# MainSchematic.net
KiCad netlist of a schematic drawn in Altium Designer
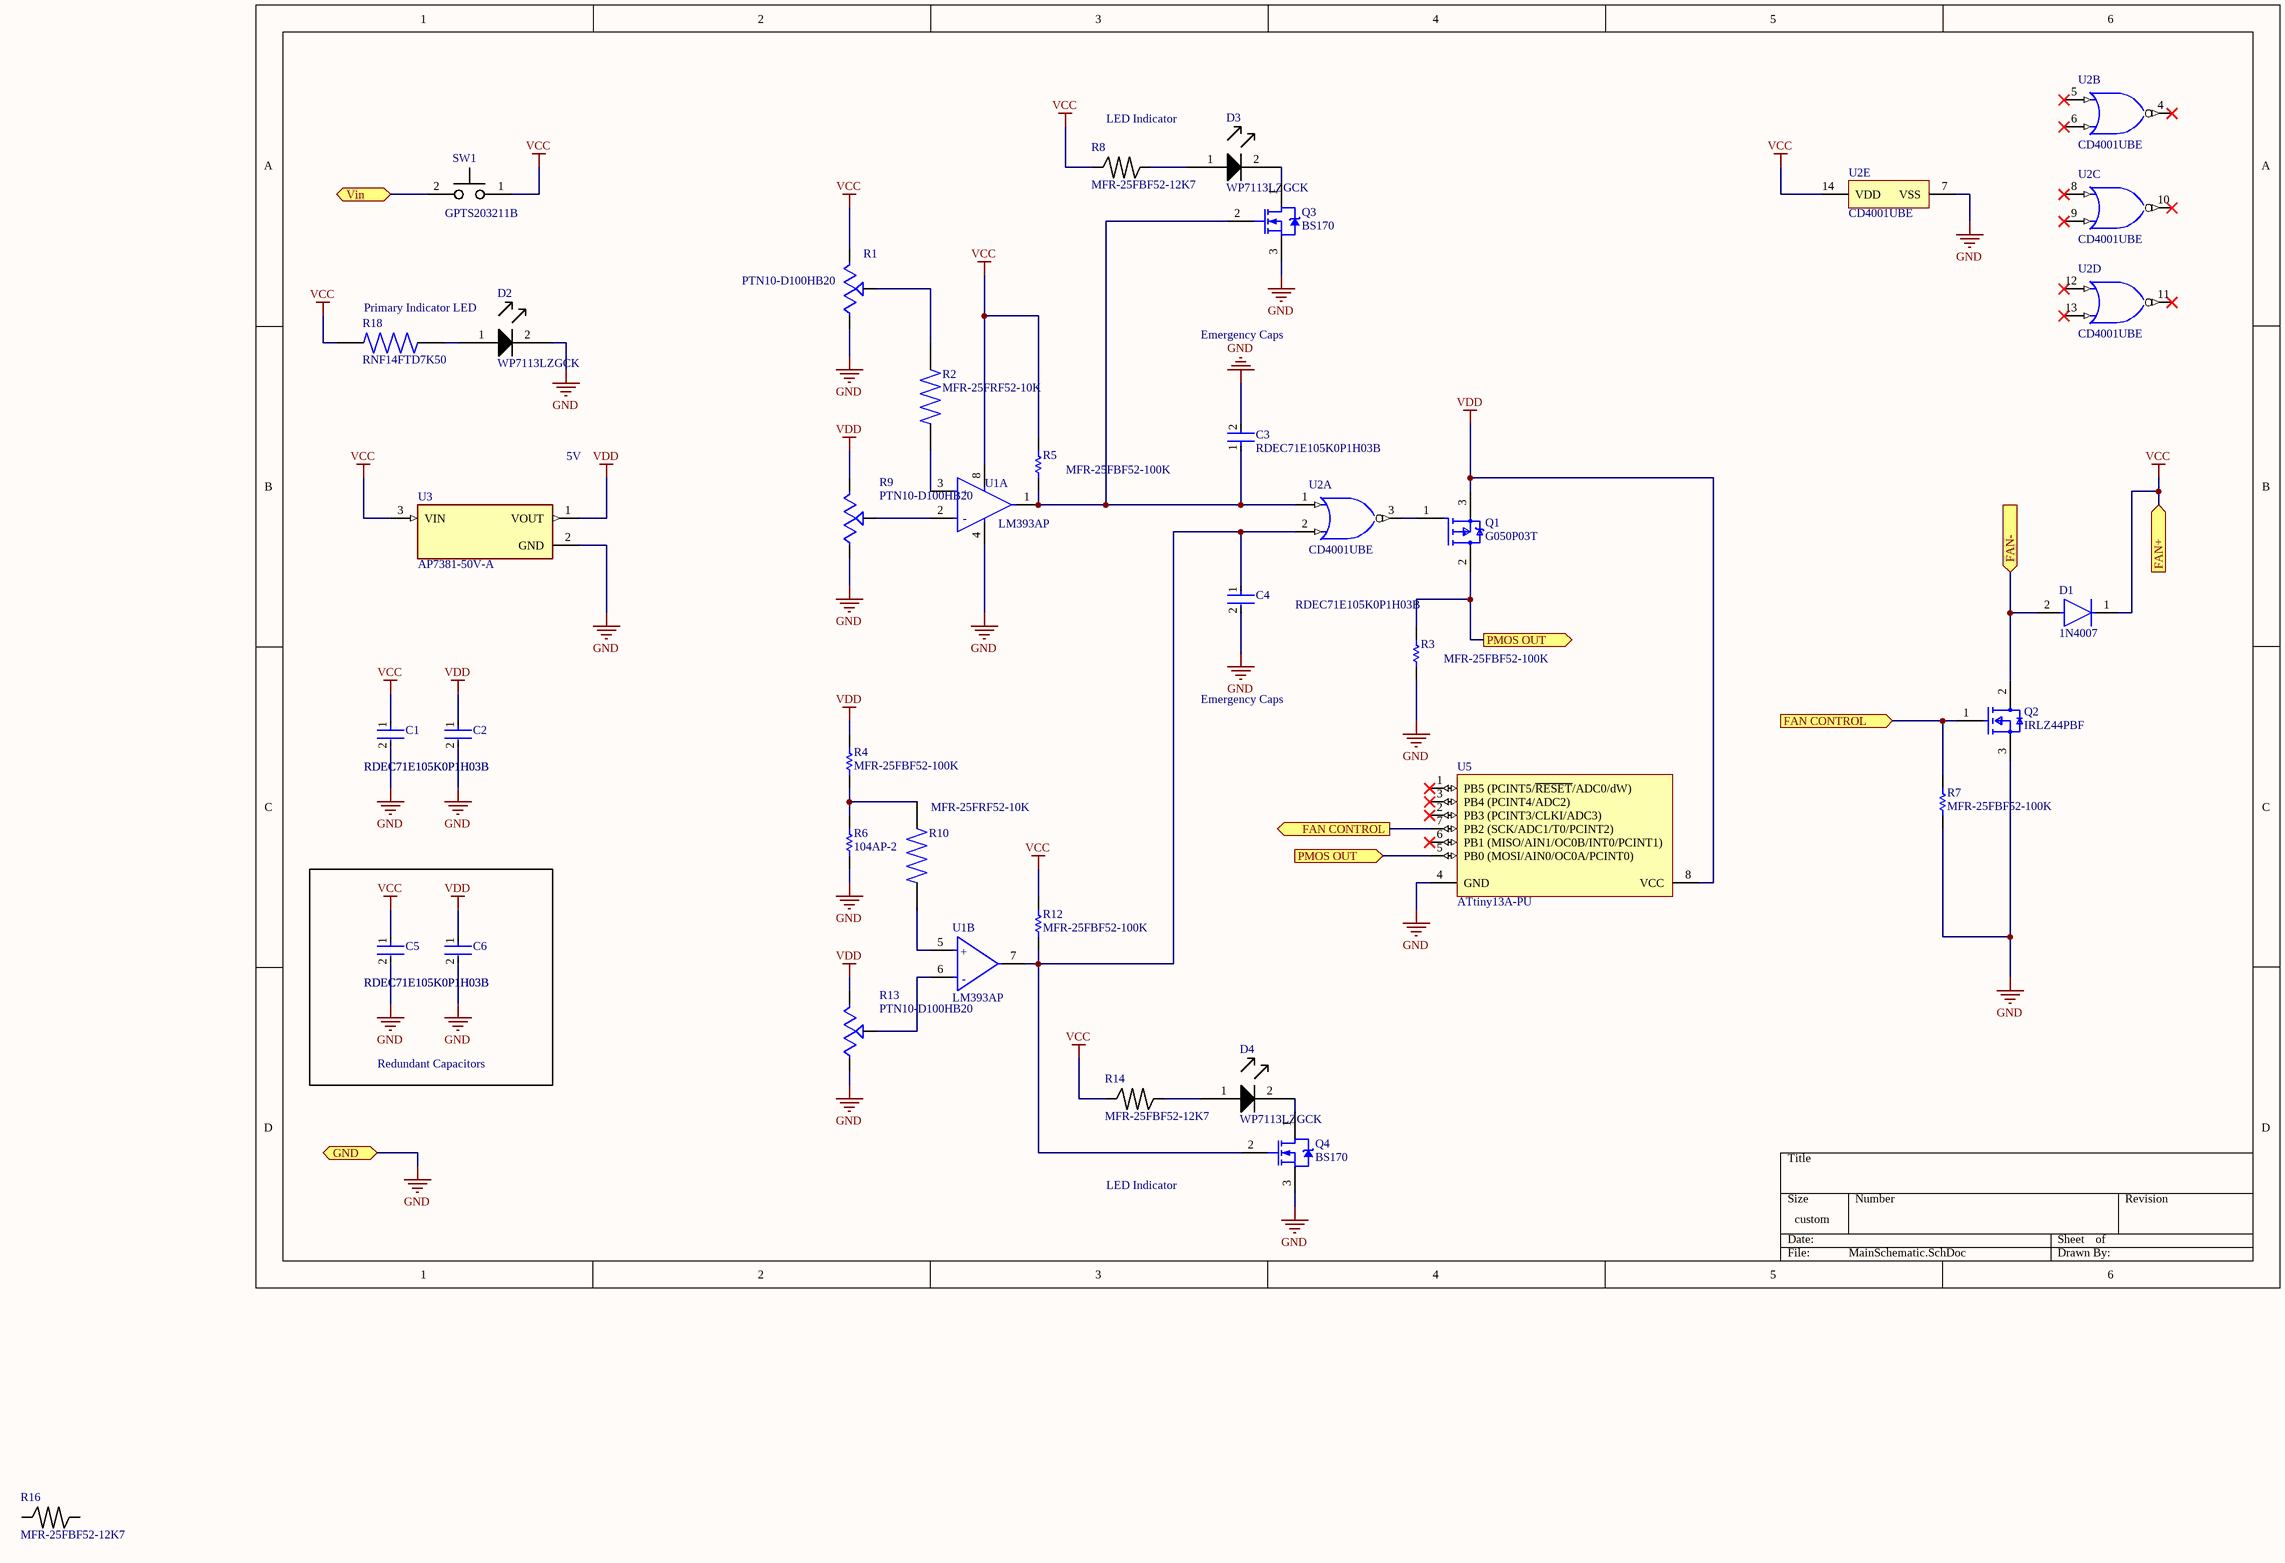
[diagram p0: MainSchematic.SchDoc]

(export (version "E")
  (design (tool "Eeschema 10.0.6"))
  (components
    (comp (ref "C1")
      (value "RDEC71E105K0P1H03B")
      (footprint "FP-RDE0P1-MFG")
      (description "Ceramic Capacitor 1uF ±10% 25V X7S Radial")
      (fields (field (name "TOLERANCE") "10%"))
      (libsource (lib "Altium Content Vault") (part "b4654b650e69147ec39a6b967a45e02"))
    )
    (comp (ref "C2")
      (value "RDEC71E105K0P1H03B")
      (footprint "FP-RDE0P1-MFG")
      (description "Ceramic Capacitor 1uF ±10% 25V X7S Radial")
      (fields (field (name "TOLERANCE") "10%"))
      (libsource (lib "Altium Content Vault") (part "b4654b650e69147ec39a6b967a45e02"))
    )
    (comp (ref "C3")
      (value "RDEC71E105K0P1H03B")
      (footprint "FP-RDE0P1-MFG")
      (description "Ceramic Capacitor 1uF ±10% 25V X7S Radial")
      (fields (field (name "TOLERANCE") "10%"))
      (libsource (lib "Altium Content Vault") (part "b4654b650e69147ec39a6b967a45e02"))
    )
    (comp (ref "C4")
      (value "RDEC71E105K0P1H03B")
      (footprint "FP-RDE0P1-MFG")
      (description "Ceramic Capacitor 1uF ±10% 25V X7S Radial")
      (fields (field (name "TOLERANCE") "10%"))
      (libsource (lib "Altium Content Vault") (part "b4654b650e69147ec39a6b967a45e02"))
    )
    (comp (ref "C5")
      (value "RDEC71E105K0P1H03B")
      (footprint "FP-RDE0P1-MFG")
      (description "Ceramic Capacitor 1uF ±10% 25V X7S Radial")
      (fields (field (name "TOLERANCE") "10%"))
      (libsource (lib "Altium Content Vault") (part "b4654b650e69147ec39a6b967a45e02"))
    )
    (comp (ref "C6")
      (value "RDEC71E105K0P1H03B")
      (footprint "FP-RDE0P1-MFG")
      (description "Ceramic Capacitor 1uF ±10% 25V X7S Radial")
      (fields (field (name "TOLERANCE") "10%"))
      (libsource (lib "Altium Content Vault") (part "b4654b650e69147ec39a6b967a45e02"))
    )
    (comp (ref "D1")
      (value "1N4007")
      (footprint "FP-1N4007-MFG")
      (description "Rectifier diode 1000 V 1 A DO-41, ,")
      (fields
        (field (name "MANUFACTURER") "Diotec")
        (field (name "OCTOPART") "https://octopart.com/1n4007-diotec-4040411")
      )
      (libsource (lib "Altium Content Vault") (part "d7152d700b627762746794eb795d46e"))
    )
    (comp (ref "D2")
      (value "WP7113LZGCK")
      (footprint "WP7113LZGCK")
      (description "Green 525nm LED Indication - Discrete 2.65V Radial")
      (libsource (lib "Schlib1") (part "WP7113LZGCK"))
    )
    (comp (ref "D3")
      (value "WP7113LZGCK")
      (footprint "WP7113LZGCK")
      (description "Green 525nm LED Indication - Discrete 2.65V Radial")
      (libsource (lib "Schlib1") (part "WP7113LZGCK"))
    )
    (comp (ref "D4")
      (value "WP7113LZGCK")
      (footprint "WP7113LZGCK")
      (description "Green 525nm LED Indication - Discrete 2.65V Radial")
      (libsource (lib "Schlib1") (part "WP7113LZGCK"))
    )
    (comp (ref "Q1")
      (value "G050P03T")
      (footprint "FP-340AT-MFG")
      (description "P-30V,-85A,RD(MAX)<5M@-10V,VTH-1")
      (libsource (lib "Altium Content Vault") (part "a653c5138454f5afaefa221b434e7dc"))
    )
    (comp (ref "Q2")
      (value "IRLZ44PBF")
      (footprint "FP-PG-TO220-3-MFG")
      (description "MOSFET N-CH 60V 50A TO220AB")
      (libsource (lib "Altium Content Vault") (part "b44c8776e10362b01251f5cff19d373"))
    )
    (comp (ref "Q3")
      (value "BS170")
      (footprint "ONSC-TO-92-3-29-11")
      (description "Small Signal MOSFET, 500 mA, 60 V, N-Channel, 3-Pin TO-92, Bulk Box")
      (fields (field (name "MANUFACTURER") "On Semiconductor"))
      (libsource (lib "Altium Content Vault") (part "ONSC-NMOS-D1G2S3-3"))
    )
    (comp (ref "Q4")
      (value "BS170")
      (footprint "ONSC-TO-92-3-29-11")
      (description "Small Signal MOSFET, 500 mA, 60 V, N-Channel, 3-Pin TO-92, Bulk Box")
      (fields (field (name "MANUFACTURER") "On Semiconductor"))
      (libsource (lib "Altium Content Vault") (part "ONSC-NMOS-D1G2S3-3"))
    )
    (comp (ref "R1")
      (value "PTN10-D100HB20")
      (footprint "TRIM_PTN10-D100HB20")
      (description "10 mm, 1 MÎ©, Linear, Through Hole, Vertical, Shaftless Hexagonal Trimmer Potentiometer")
      (fields (field (name "MF") "CUI Devices"))
      (libsource (lib "PTN10-D100HB20") (part "PTN10-D100HB20"))
    )
    (comp (ref "R2")
      (value "MFR-25FRF52-10K")
      (footprint "RESAD1100W55L680D260")
      (description "RES 280K OHM 1/4W 1% AXIAL")
      (libsource (lib "MFR-25FRF52-10K") (part "MFR-25FRF52-10K"))
    )
    (comp (ref "R3")
      (value "MFR-25FBF52-100K")
      (footprint "RESA60-630X240")
      (description "Axial Resistor, 100 KOhm, +/- 1%, 0.25 W, -55 to 155 degC, 2-Pin THD, RoHS, Bulk")
      (fields (field (name "TOLERANCE") "1%"))
      (libsource (lib "Altium Content Vault") (part "RES-2"))
    )
    (comp (ref "R4")
      (value "MFR-25FBF52-100K")
      (footprint "RESA60-630X240")
      (description "Axial Resistor, 100 KOhm, +/- 1%, 0.25 W, -55 to 155 degC, 2-Pin THD, RoHS, Bulk")
      (fields (field (name "TOLERANCE") "1%"))
      (libsource (lib "Altium Content Vault") (part "RES-2"))
    )
    (comp (ref "R5")
      (value "MFR-25FBF52-100K")
      (footprint "RESA60-630X240")
      (description "Axial Resistor, 100 KOhm, +/- 1%, 0.25 W, -55 to 155 degC, 2-Pin THD, RoHS, Bulk")
      (fields (field (name "TOLERANCE") "1%"))
      (libsource (lib "Altium Content Vault") (part "RES-2"))
    )
    (comp (ref "R6")
      (value "104AP-2")
      (footprint "RESA60-630X240")
      (description "NTC THERMISTORS 100KOHM 0.5%")
      (fields (field (name "TOLERANCE") "1%"))
      (libsource (lib "Altium Content Vault") (part "RES-2"))
    )
    (comp (ref "R7")
      (value "MFR-25FBF52-100K")
      (footprint "RESA60-630X240")
      (description "Axial Resistor, 100 KOhm, +/- 1%, 0.25 W, -55 to 155 degC, 2-Pin THD, RoHS, Bulk")
      (fields (field (name "TOLERANCE") "1%"))
      (libsource (lib "Altium Content Vault") (part "RES-2"))
    )
    (comp (ref "R8")
      (value "MFR-25FBF52-12K7")
      (footprint "RESAD1100W55L680D260")
      (description "RES 12.7K OHM 1% 1/4W AXIAL")
      (libsource (lib "Schlib1") (part "MFR-25FBF52-12K7"))
    )
    (comp (ref "R9")
      (value "PTN10-D100HB20")
      (footprint "TRIM_PTN10-D100HB20")
      (description "10 mm, 1 MÎ©, Linear, Through Hole, Vertical, Shaftless Hexagonal Trimmer Potentiometer")
      (fields (field (name "MF") "CUI Devices"))
      (libsource (lib "PTN10-D100HB20") (part "PTN10-D100HB20"))
    )
    (comp (ref "R10")
      (value "MFR-25FRF52-10K")
      (footprint "RESAD1100W55L680D260")
      (description "RES 280K OHM 1/4W 1% AXIAL")
      (libsource (lib "MFR-25FRF52-10K") (part "MFR-25FRF52-10K"))
    )
    (comp (ref "R12")
      (value "MFR-25FBF52-100K")
      (footprint "RESA60-630X240")
      (description "Axial Resistor, 100 KOhm, +/- 1%, 0.25 W, -55 to 155 degC, 2-Pin THD, RoHS, Bulk")
      (fields (field (name "TOLERANCE") "1%"))
      (libsource (lib "Altium Content Vault") (part "RES-2"))
    )
    (comp (ref "R13")
      (value "PTN10-D100HB20")
      (footprint "TRIM_PTN10-D100HB20")
      (description "10 mm, 1 MÎ©, Linear, Through Hole, Vertical, Shaftless Hexagonal Trimmer Potentiometer")
      (fields (field (name "MF") "CUI Devices"))
      (libsource (lib "PTN10-D100HB20") (part "PTN10-D100HB20"))
    )
    (comp (ref "R14")
      (value "MFR-25FBF52-12K7")
      (footprint "RESAD1100W55L680D260")
      (description "RES 12.7K OHM 1% 1/4W AXIAL")
      (libsource (lib "Schlib1") (part "MFR-25FBF52-12K7"))
    )
    (comp (ref "R16")
      (value "MFR-25FBF52-12K7")
      (footprint "RESAD1100W55L680D260")
      (description "RES 12.7K OHM 1% 1/4W AXIAL")
      (libsource (lib "Schlib1") (part "MFR-25FBF52-12K7"))
    )
    (comp (ref "R18")
      (value "RNF14FTD7K50")
      (footprint "RESAD1100W55L680D260")
      (description "RES 280K OHM 1/4W 1% AXIAL")
      (fields (field (name "MP") "MFR-25FRF52-10K"))
      (libsource (lib "MFR-25FRF52-10K") (part "MFR-25FRF52-10K"))
    )
    (comp (ref "SW1")
      (value "GPTS203211B")
      (footprint "GPTS203211B")
      (description "Pushbutton Switch SPST Standard Through Hole")
      (libsource (lib "Schlib1") (part "GPTS203211B"))
    )
    (comp (ref "U1")
      (value "LM393AP")
      (footprint "FP-P0008A-MFG")
      (description "IC DUAL DIFF COMPARATOR 8-DIP")
      (libsource (lib "Altium Content Vault") (part "28ffe1f6a599f08a8494cd30af5fdb3"))
    )
    (comp (ref "U2")
      (value "CD4001UBE")
      (footprint "N0014A")
      (description "CMOS Quad 2-Input NOR Gate, N0014A, TUBE")
      (fields
        (field (name "MANUFACTURER") "Texas Instruments")
        (field (name "GENERIC PART NUMBER") "CD4001UB")
      )
      (libsource (lib "Altium Content Vault") (part "TI-CD4001UB-N0014A-14"))
    )
    (comp (ref "U3")
      (value "AP7381-50V-A")
      (footprint "TO92254P480H870-3")
      (description "Linear Voltage Regulator IC Positive Fixed 1 Output 150mA TO-92")
      (fields (field (name "MF") "Diodes Inc.") (field (name "DIGI-KEY_PART_NUMBER") "AP7381-50V-ADICT-ND"))
      (libsource (lib "AP7381-50V-A") (part "AP7381-50V-A"))
    )
    (comp (ref "U5")
      (value "ATtiny13A-PU")
      (footprint "8P3")
      (libsource (lib "Altium Content Vault") (part "MC-8B-ATT13A-IL8"))
    )
  )
  (nets
    (net (code "1") (name "/FAN CONTROL") (class "Default")
      (node (ref "Q2") (pin "1") (pinfunction "G_1") (pintype "passive"))
      (node (ref "R7") (pin "2") (pinfunction "2_2") (pintype "passive"))
      (node (ref "U5") (pin "7") (pinfunction "PB2_(SCK/ADC1/T0/PCINT2)_7") (pintype "bidirectional"))
    )
    (net (code "2") (name "/FAN-") (class "Default")
      (node (ref "D1") (pin "2") (pinfunction "A_2") (pintype "passive"))
      (node (ref "Q2") (pin "2") (pinfunction "D_2") (pintype "passive"))
    )
    (net (code "3") (name "/PMOS OUT") (class "Default")
      (node (ref "Q1") (pin "2") (pinfunction "D_2") (pintype "passive"))
      (node (ref "R3") (pin "2") (pinfunction "2_2") (pintype "passive"))
      (node (ref "U5") (pin "5") (pinfunction "PB0_(MOSI/AIN0/OC0A/PCINT0)_5") (pintype "bidirectional"))
    )
    (net (code "4") (name "/Vin") (class "Default")
      (node (ref "SW1") (pin "2") (pinfunction "2_2") (pintype "passive"))
    )
    (net (code "5") (name "GND") (class "Default")
      (node (ref "C1") (pin "2") (pinfunction "2_2") (pintype "passive"))
      (node (ref "C2") (pin "2") (pinfunction "2_2") (pintype "passive"))
      (node (ref "C3") (pin "2") (pinfunction "2_2") (pintype "passive"))
      (node (ref "C4") (pin "2") (pinfunction "2_2") (pintype "passive"))
      (node (ref "C5") (pin "2") (pinfunction "2_2") (pintype "passive"))
      (node (ref "C6") (pin "2") (pinfunction "2_2") (pintype "passive"))
      (node (ref "D2") (pin "2") (pinfunction "2_2") (pintype "passive"))
      (node (ref "Q2") (pin "3") (pinfunction "S_3") (pintype "passive"))
      (node (ref "Q3") (pin "3") (pinfunction "S_3") (pintype "passive"))
      (node (ref "Q4") (pin "3") (pinfunction "S_3") (pintype "passive"))
      (node (ref "R1") (pin "A") (pinfunction "INITIAL_A") (pintype "passive"))
      (node (ref "R13") (pin "A") (pinfunction "INITIAL_A") (pintype "passive"))
      (node (ref "R3") (pin "1") (pinfunction "1_1") (pintype "passive"))
      (node (ref "R6") (pin "1") (pinfunction "1_1") (pintype "passive"))
      (node (ref "R7") (pin "1") (pinfunction "1_1") (pintype "passive"))
      (node (ref "R9") (pin "A") (pinfunction "INITIAL_A") (pintype "passive"))
      (node (ref "U1") (pin "4") (pinfunction "GND_4") (pintype "power_in"))
      (node (ref "U2") (pin "7") (pinfunction "VSS_7") (pintype "power_in"))
      (node (ref "U3") (pin "2") (pinfunction "GND_2") (pintype "power_in"))
      (node (ref "U5") (pin "4") (pinfunction "GND_4") (pintype "power_in"))
    )
    (net (code "6") (name "Net-(D2-Pad1)") (class "Default")
      (node (ref "D2") (pin "1") (pinfunction "1_1") (pintype "passive"))
      (node (ref "R18") (pin "2") (pinfunction "2_2") (pintype "passive"))
    )
    (net (code "7") (name "Net-(D3-Pad1)") (class "Default")
      (node (ref "D3") (pin "1") (pinfunction "1_1") (pintype "passive"))
      (node (ref "R8") (pin "2") (pinfunction "2_2") (pintype "passive"))
    )
    (net (code "8") (name "Net-(D4-Pad1)") (class "Default")
      (node (ref "D4") (pin "1") (pinfunction "1_1") (pintype "passive"))
      (node (ref "R14") (pin "2") (pinfunction "2_2") (pintype "passive"))
    )
    (net (code "9") (name "Net-(Q1-G)") (class "Default")
      (node (ref "Q1") (pin "1") (pinfunction "G_1") (pintype "passive"))
      (node (ref "U2") (pin "3") (pinfunction "J_3") (pintype "output"))
    )
    (net (code "10") (name "Net-(Q3-D)") (class "Default")
      (node (ref "D3") (pin "2") (pinfunction "2_2") (pintype "passive"))
      (node (ref "Q3") (pin "1") (pinfunction "D_1") (pintype "passive"))
    )
    (net (code "11") (name "Net-(Q3-G)") (class "Default")
      (node (ref "C3") (pin "1") (pinfunction "1_1") (pintype "passive"))
      (node (ref "Q3") (pin "2") (pinfunction "G_2") (pintype "passive"))
      (node (ref "R5") (pin "1") (pinfunction "1_1") (pintype "passive"))
      (node (ref "U1") (pin "1") (pinfunction "1OUT_1") (pintype "passive"))
      (node (ref "U2") (pin "1") (pinfunction "A_1") (pintype "input"))
    )
    (net (code "12") (name "Net-(Q4-D)") (class "Default")
      (node (ref "D4") (pin "2") (pinfunction "2_2") (pintype "passive"))
      (node (ref "Q4") (pin "1") (pinfunction "D_1") (pintype "passive"))
    )
    (net (code "13") (name "Net-(Q4-G)") (class "Default")
      (node (ref "C4") (pin "1") (pinfunction "1_1") (pintype "passive"))
      (node (ref "Q4") (pin "2") (pinfunction "G_2") (pintype "passive"))
      (node (ref "R12") (pin "1") (pinfunction "1_1") (pintype "passive"))
      (node (ref "U1") (pin "7") (pinfunction "2OUT_7") (pintype "passive"))
      (node (ref "U2") (pin "2") (pinfunction "B_2") (pintype "input"))
    )
    (net (code "14") (name "Net-(R1-WIPER)") (class "Default")
      (node (ref "R1") (pin "S") (pinfunction "WIPER_S") (pintype "passive"))
      (node (ref "R2") (pin "1") (pinfunction "1_1") (pintype "passive"))
    )
    (net (code "15") (name "Net-(R9-WIPER)") (class "Default")
      (node (ref "R9") (pin "S") (pinfunction "WIPER_S") (pintype "passive"))
      (node (ref "U1") (pin "2") (pinfunction "1IN-_2") (pintype "tri_state"))
    )
    (net (code "16") (name "Net-(R10-Pad1)") (class "Default")
      (node (ref "R10") (pin "1") (pinfunction "1_1") (pintype "passive"))
      (node (ref "R4") (pin "1") (pinfunction "1_1") (pintype "passive"))
      (node (ref "R6") (pin "2") (pinfunction "2_2") (pintype "passive"))
    )
    (net (code "17") (name "Net-(R13-WIPER)") (class "Default")
      (node (ref "R13") (pin "S") (pinfunction "WIPER_S") (pintype "passive"))
      (node (ref "U1") (pin "6") (pinfunction "2IN-_6") (pintype "tri_state"))
    )
    (net (code "18") (name "Net-(U1A-1IN+)") (class "Default")
      (node (ref "R2") (pin "2") (pinfunction "2_2") (pintype "passive"))
      (node (ref "U1") (pin "3") (pinfunction "1IN+_3") (pintype "tri_state"))
    )
    (net (code "19") (name "Net-(U1B-2IN+)") (class "Default")
      (node (ref "R10") (pin "2") (pinfunction "2_2") (pintype "passive"))
      (node (ref "U1") (pin "5") (pinfunction "2IN+_5") (pintype "tri_state"))
    )
    (net (code "20") (name "VCC") (class "Default")
      (node (ref "C1") (pin "1") (pinfunction "1_1") (pintype "passive"))
      (node (ref "C5") (pin "1") (pinfunction "1_1") (pintype "passive"))
      (node (ref "D1") (pin "1") (pinfunction "C_1") (pintype "passive"))
      (node (ref "R1") (pin "E") (pinfunction "FINAL_E") (pintype "passive"))
      (node (ref "R12") (pin "2") (pinfunction "2_2") (pintype "passive"))
      (node (ref "R14") (pin "1") (pinfunction "1_1") (pintype "passive"))
      (node (ref "R18") (pin "1") (pinfunction "1_1") (pintype "passive"))
      (node (ref "R5") (pin "2") (pinfunction "2_2") (pintype "passive"))
      (node (ref "R8") (pin "1") (pinfunction "1_1") (pintype "passive"))
      (node (ref "SW1") (pin "1") (pinfunction "1_1") (pintype "passive"))
      (node (ref "U1") (pin "8") (pinfunction "VCC_8") (pintype "power_in"))
      (node (ref "U2") (pin "14") (pinfunction "VDD_14") (pintype "power_in"))
      (node (ref "U3") (pin "3") (pinfunction "VIN_3") (pintype "input"))
    )
    (net (code "21") (name "VDD") (class "Default")
      (node (ref "C2") (pin "1") (pinfunction "1_1") (pintype "passive"))
      (node (ref "C6") (pin "1") (pinfunction "1_1") (pintype "passive"))
      (node (ref "Q1") (pin "3") (pinfunction "S_3") (pintype "passive"))
      (node (ref "R13") (pin "E") (pinfunction "FINAL_E") (pintype "passive"))
      (node (ref "R4") (pin "2") (pinfunction "2_2") (pintype "passive"))
      (node (ref "R9") (pin "E") (pinfunction "FINAL_E") (pintype "passive"))
      (node (ref "U3") (pin "1") (pinfunction "VOUT_1") (pintype "output"))
      (node (ref "U5") (pin "8") (pinfunction "VCC_8") (pintype "power_in"))
    )
    (net (code "22") (name "unconnected-(R16-Pad1)") (class "Default")
      (node (ref "R16") (pin "1") (pinfunction "1_1") (pintype "passive"))
    )
    (net (code "23") (name "unconnected-(R16-Pad2)") (class "Default")
      (node (ref "R16") (pin "2") (pinfunction "2_2") (pintype "passive"))
    )
    (net (code "24") (name "unconnected-(U2B-C-Pad5)") (class "Default")
      (node (ref "U2") (pin "5") (pinfunction "C_5") (pintype "input+no_connect"))
    )
    (net (code "25") (name "unconnected-(U2B-D-Pad6)") (class "Default")
      (node (ref "U2") (pin "6") (pinfunction "D_6") (pintype "input+no_connect"))
    )
    (net (code "26") (name "unconnected-(U2B-K-Pad4)") (class "Default")
      (node (ref "U2") (pin "4") (pinfunction "K_4") (pintype "output+no_connect"))
    )
    (net (code "27") (name "unconnected-(U2C-E-Pad8)") (class "Default")
      (node (ref "U2") (pin "8") (pinfunction "E_8") (pintype "input+no_connect"))
    )
    (net (code "28") (name "unconnected-(U2C-F-Pad9)") (class "Default")
      (node (ref "U2") (pin "9") (pinfunction "F_9") (pintype "input+no_connect"))
    )
    (net (code "29") (name "unconnected-(U2C-L-Pad10)") (class "Default")
      (node (ref "U2") (pin "10") (pinfunction "L_10") (pintype "output+no_connect"))
    )
    (net (code "30") (name "unconnected-(U2D-G-Pad12)") (class "Default")
      (node (ref "U2") (pin "12") (pinfunction "G_12") (pintype "input+no_connect"))
    )
    (net (code "31") (name "unconnected-(U2D-H-Pad13)") (class "Default")
      (node (ref "U2") (pin "13") (pinfunction "H_13") (pintype "input+no_connect"))
    )
    (net (code "32") (name "unconnected-(U2D-M-Pad11)") (class "Default")
      (node (ref "U2") (pin "11") (pinfunction "M_11") (pintype "output+no_connect"))
    )
    (net (code "33") (name "unconnected-(U5-PB1_(MISO{slash}AIN1{slash}OC0B{slash}INT0{slash}PCINT1)-Pad6)") (class "Default")
      (node (ref "U5") (pin "6") (pinfunction "PB1_(MISO/AIN1/OC0B/INT0/PCINT1)_6") (pintype "bidirectional+no_connect"))
    )
    (net (code "34") (name "unconnected-(U5-PB3_(PCINT3{slash}CLKI{slash}ADC3)-Pad2)") (class "Default")
      (node (ref "U5") (pin "2") (pinfunction "PB3_(PCINT3/CLKI/ADC3)_2") (pintype "bidirectional+no_connect"))
    )
    (net (code "35") (name "unconnected-(U5-PB4_(PCINT4{slash}ADC2)-Pad3)") (class "Default")
      (node (ref "U5") (pin "3") (pinfunction "PB4_(PCINT4/ADC2)_3") (pintype "bidirectional+no_connect"))
    )
    (net (code "36") (name "unconnected-(U5-PB5_(PCINT5{slash}~{RESET}{slash}ADC0{slash}dW)-Pad1)") (class "Default")
      (node (ref "U5") (pin "1") (pinfunction "PB5_(PCINT5/~{RESET}/ADC0/dW)_1") (pintype "bidirectional+no_connect"))
    )
  )
)
